# FPC_to_wires.net
KiCad netlist of a schematic drawn in Altium Designer
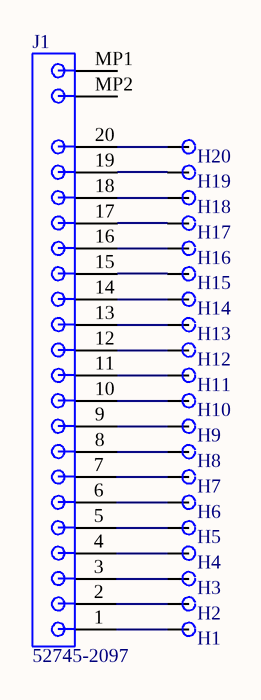
[diagram p0: FPC_to_wires.SchDoc]

(export (version "E")
  (design (tool "Eeschema 10.0.6"))
  (components
    (comp (ref "H1") (value "PAD") (footprint "PAD") (libsource (lib "sample_holder_library") (part "PAD")))
    (comp (ref "H2") (value "PAD") (footprint "PAD") (libsource (lib "sample_holder_library") (part "PAD")))
    (comp (ref "H3") (value "PAD") (footprint "PAD") (libsource (lib "sample_holder_library") (part "PAD")))
    (comp (ref "H4") (value "PAD") (footprint "PAD") (libsource (lib "sample_holder_library") (part "PAD")))
    (comp (ref "H5") (value "PAD") (footprint "PAD") (libsource (lib "sample_holder_library") (part "PAD")))
    (comp (ref "H6") (value "PAD") (footprint "PAD") (libsource (lib "sample_holder_library") (part "PAD")))
    (comp (ref "H7") (value "PAD") (footprint "PAD") (libsource (lib "sample_holder_library") (part "PAD")))
    (comp (ref "H8") (value "PAD") (footprint "PAD") (libsource (lib "sample_holder_library") (part "PAD")))
    (comp (ref "H9") (value "PAD") (footprint "PAD") (libsource (lib "sample_holder_library") (part "PAD")))
    (comp (ref "H10") (value "PAD") (footprint "PAD") (libsource (lib "sample_holder_library") (part "PAD")))
    (comp (ref "H11") (value "PAD") (footprint "PAD") (libsource (lib "sample_holder_library") (part "PAD")))
    (comp (ref "H12") (value "PAD") (footprint "PAD") (libsource (lib "sample_holder_library") (part "PAD")))
    (comp (ref "H13") (value "PAD") (footprint "PAD") (libsource (lib "sample_holder_library") (part "PAD")))
    (comp (ref "H14") (value "PAD") (footprint "PAD") (libsource (lib "sample_holder_library") (part "PAD")))
    (comp (ref "H15") (value "PAD") (footprint "PAD") (libsource (lib "sample_holder_library") (part "PAD")))
    (comp (ref "H16") (value "PAD") (footprint "PAD") (libsource (lib "sample_holder_library") (part "PAD")))
    (comp (ref "H17") (value "PAD") (footprint "PAD") (libsource (lib "sample_holder_library") (part "PAD")))
    (comp (ref "H18") (value "PAD") (footprint "PAD") (libsource (lib "sample_holder_library") (part "PAD")))
    (comp (ref "H19") (value "PAD") (footprint "PAD") (libsource (lib "sample_holder_library") (part "PAD")))
    (comp (ref "H20") (value "PAD") (footprint "PAD") (libsource (lib "sample_holder_library") (part "PAD")))
    (comp (ref "J1")
      (value "52745-2097")
      (footprint "MOLX-52745-2097")
      (fields (field (name "MANUFACTURER") "Molex"))
      (libsource (lib "sample_holder_library") (part "52745-2097"))
    )
  )
  (nets
    (net (code "1") (name "Net-(H1-Pad1)") (class "Default")
      (node (ref "H1") (pin "1") (pinfunction "1_1") (pintype "passive"))
      (node (ref "J1") (pin "1") (pinfunction "1_1") (pintype "passive"))
    )
    (net (code "2") (name "Net-(H2-Pad1)") (class "Default")
      (node (ref "H2") (pin "1") (pinfunction "1_1") (pintype "passive"))
      (node (ref "J1") (pin "2") (pinfunction "2_2") (pintype "passive"))
    )
    (net (code "3") (name "Net-(H3-Pad1)") (class "Default")
      (node (ref "H3") (pin "1") (pinfunction "1_1") (pintype "passive"))
      (node (ref "J1") (pin "3") (pinfunction "3_3") (pintype "passive"))
    )
    (net (code "4") (name "Net-(H4-Pad1)") (class "Default")
      (node (ref "H4") (pin "1") (pinfunction "1_1") (pintype "passive"))
      (node (ref "J1") (pin "4") (pinfunction "4_4") (pintype "passive"))
    )
    (net (code "5") (name "Net-(H5-Pad1)") (class "Default")
      (node (ref "H5") (pin "1") (pinfunction "1_1") (pintype "passive"))
      (node (ref "J1") (pin "5") (pinfunction "5_5") (pintype "passive"))
    )
    (net (code "6") (name "Net-(H6-Pad1)") (class "Default")
      (node (ref "H6") (pin "1") (pinfunction "1_1") (pintype "passive"))
      (node (ref "J1") (pin "6") (pinfunction "6_6") (pintype "passive"))
    )
    (net (code "7") (name "Net-(H7-Pad1)") (class "Default")
      (node (ref "H7") (pin "1") (pinfunction "1_1") (pintype "passive"))
      (node (ref "J1") (pin "7") (pinfunction "7_7") (pintype "passive"))
    )
    (net (code "8") (name "Net-(H8-Pad1)") (class "Default")
      (node (ref "H8") (pin "1") (pinfunction "1_1") (pintype "passive"))
      (node (ref "J1") (pin "8") (pinfunction "8_8") (pintype "passive"))
    )
    (net (code "9") (name "Net-(H9-Pad1)") (class "Default")
      (node (ref "H9") (pin "1") (pinfunction "1_1") (pintype "passive"))
      (node (ref "J1") (pin "9") (pinfunction "9_9") (pintype "passive"))
    )
    (net (code "10") (name "Net-(H10-Pad1)") (class "Default")
      (node (ref "H10") (pin "1") (pinfunction "1_1") (pintype "passive"))
      (node (ref "J1") (pin "10") (pinfunction "10_10") (pintype "passive"))
    )
    (net (code "11") (name "Net-(H11-Pad1)") (class "Default")
      (node (ref "H11") (pin "1") (pinfunction "1_1") (pintype "passive"))
      (node (ref "J1") (pin "11") (pinfunction "11_11") (pintype "passive"))
    )
    (net (code "12") (name "Net-(H12-Pad1)") (class "Default")
      (node (ref "H12") (pin "1") (pinfunction "1_1") (pintype "passive"))
      (node (ref "J1") (pin "12") (pinfunction "12_12") (pintype "passive"))
    )
    (net (code "13") (name "Net-(H13-Pad1)") (class "Default")
      (node (ref "H13") (pin "1") (pinfunction "1_1") (pintype "passive"))
      (node (ref "J1") (pin "13") (pinfunction "13_13") (pintype "passive"))
    )
    (net (code "14") (name "Net-(H14-Pad1)") (class "Default")
      (node (ref "H14") (pin "1") (pinfunction "1_1") (pintype "passive"))
      (node (ref "J1") (pin "14") (pinfunction "14_14") (pintype "passive"))
    )
    (net (code "15") (name "Net-(H15-Pad1)") (class "Default")
      (node (ref "H15") (pin "1") (pinfunction "1_1") (pintype "passive"))
      (node (ref "J1") (pin "15") (pinfunction "15_15") (pintype "passive"))
    )
    (net (code "16") (name "Net-(H16-Pad1)") (class "Default")
      (node (ref "H16") (pin "1") (pinfunction "1_1") (pintype "passive"))
      (node (ref "J1") (pin "16") (pinfunction "16_16") (pintype "passive"))
    )
    (net (code "17") (name "Net-(H17-Pad1)") (class "Default")
      (node (ref "H17") (pin "1") (pinfunction "1_1") (pintype "passive"))
      (node (ref "J1") (pin "17") (pinfunction "17_17") (pintype "passive"))
    )
    (net (code "18") (name "Net-(H18-Pad1)") (class "Default")
      (node (ref "H18") (pin "1") (pinfunction "1_1") (pintype "passive"))
      (node (ref "J1") (pin "18") (pinfunction "18_18") (pintype "passive"))
    )
    (net (code "19") (name "Net-(H19-Pad1)") (class "Default")
      (node (ref "H19") (pin "1") (pinfunction "1_1") (pintype "passive"))
      (node (ref "J1") (pin "19") (pinfunction "19_19") (pintype "passive"))
    )
    (net (code "20") (name "Net-(H20-Pad1)") (class "Default")
      (node (ref "H20") (pin "1") (pinfunction "1_1") (pintype "passive"))
      (node (ref "J1") (pin "20") (pinfunction "20_20") (pintype "passive"))
    )
    (net (code "21") (name "unconnected-(J1-PadMP1)") (class "Default")
      (node (ref "J1") (pin "MP1") (pinfunction "MP1_MP1") (pintype "passive"))
    )
    (net (code "22") (name "unconnected-(J1-PadMP2)") (class "Default")
      (node (ref "J1") (pin "MP2") (pinfunction "MP2_MP2") (pintype "passive"))
    )
  )
)
